# stm32f030f4p6_board.net
KiCad netlist of a schematic drawn in EasyEDA Pro
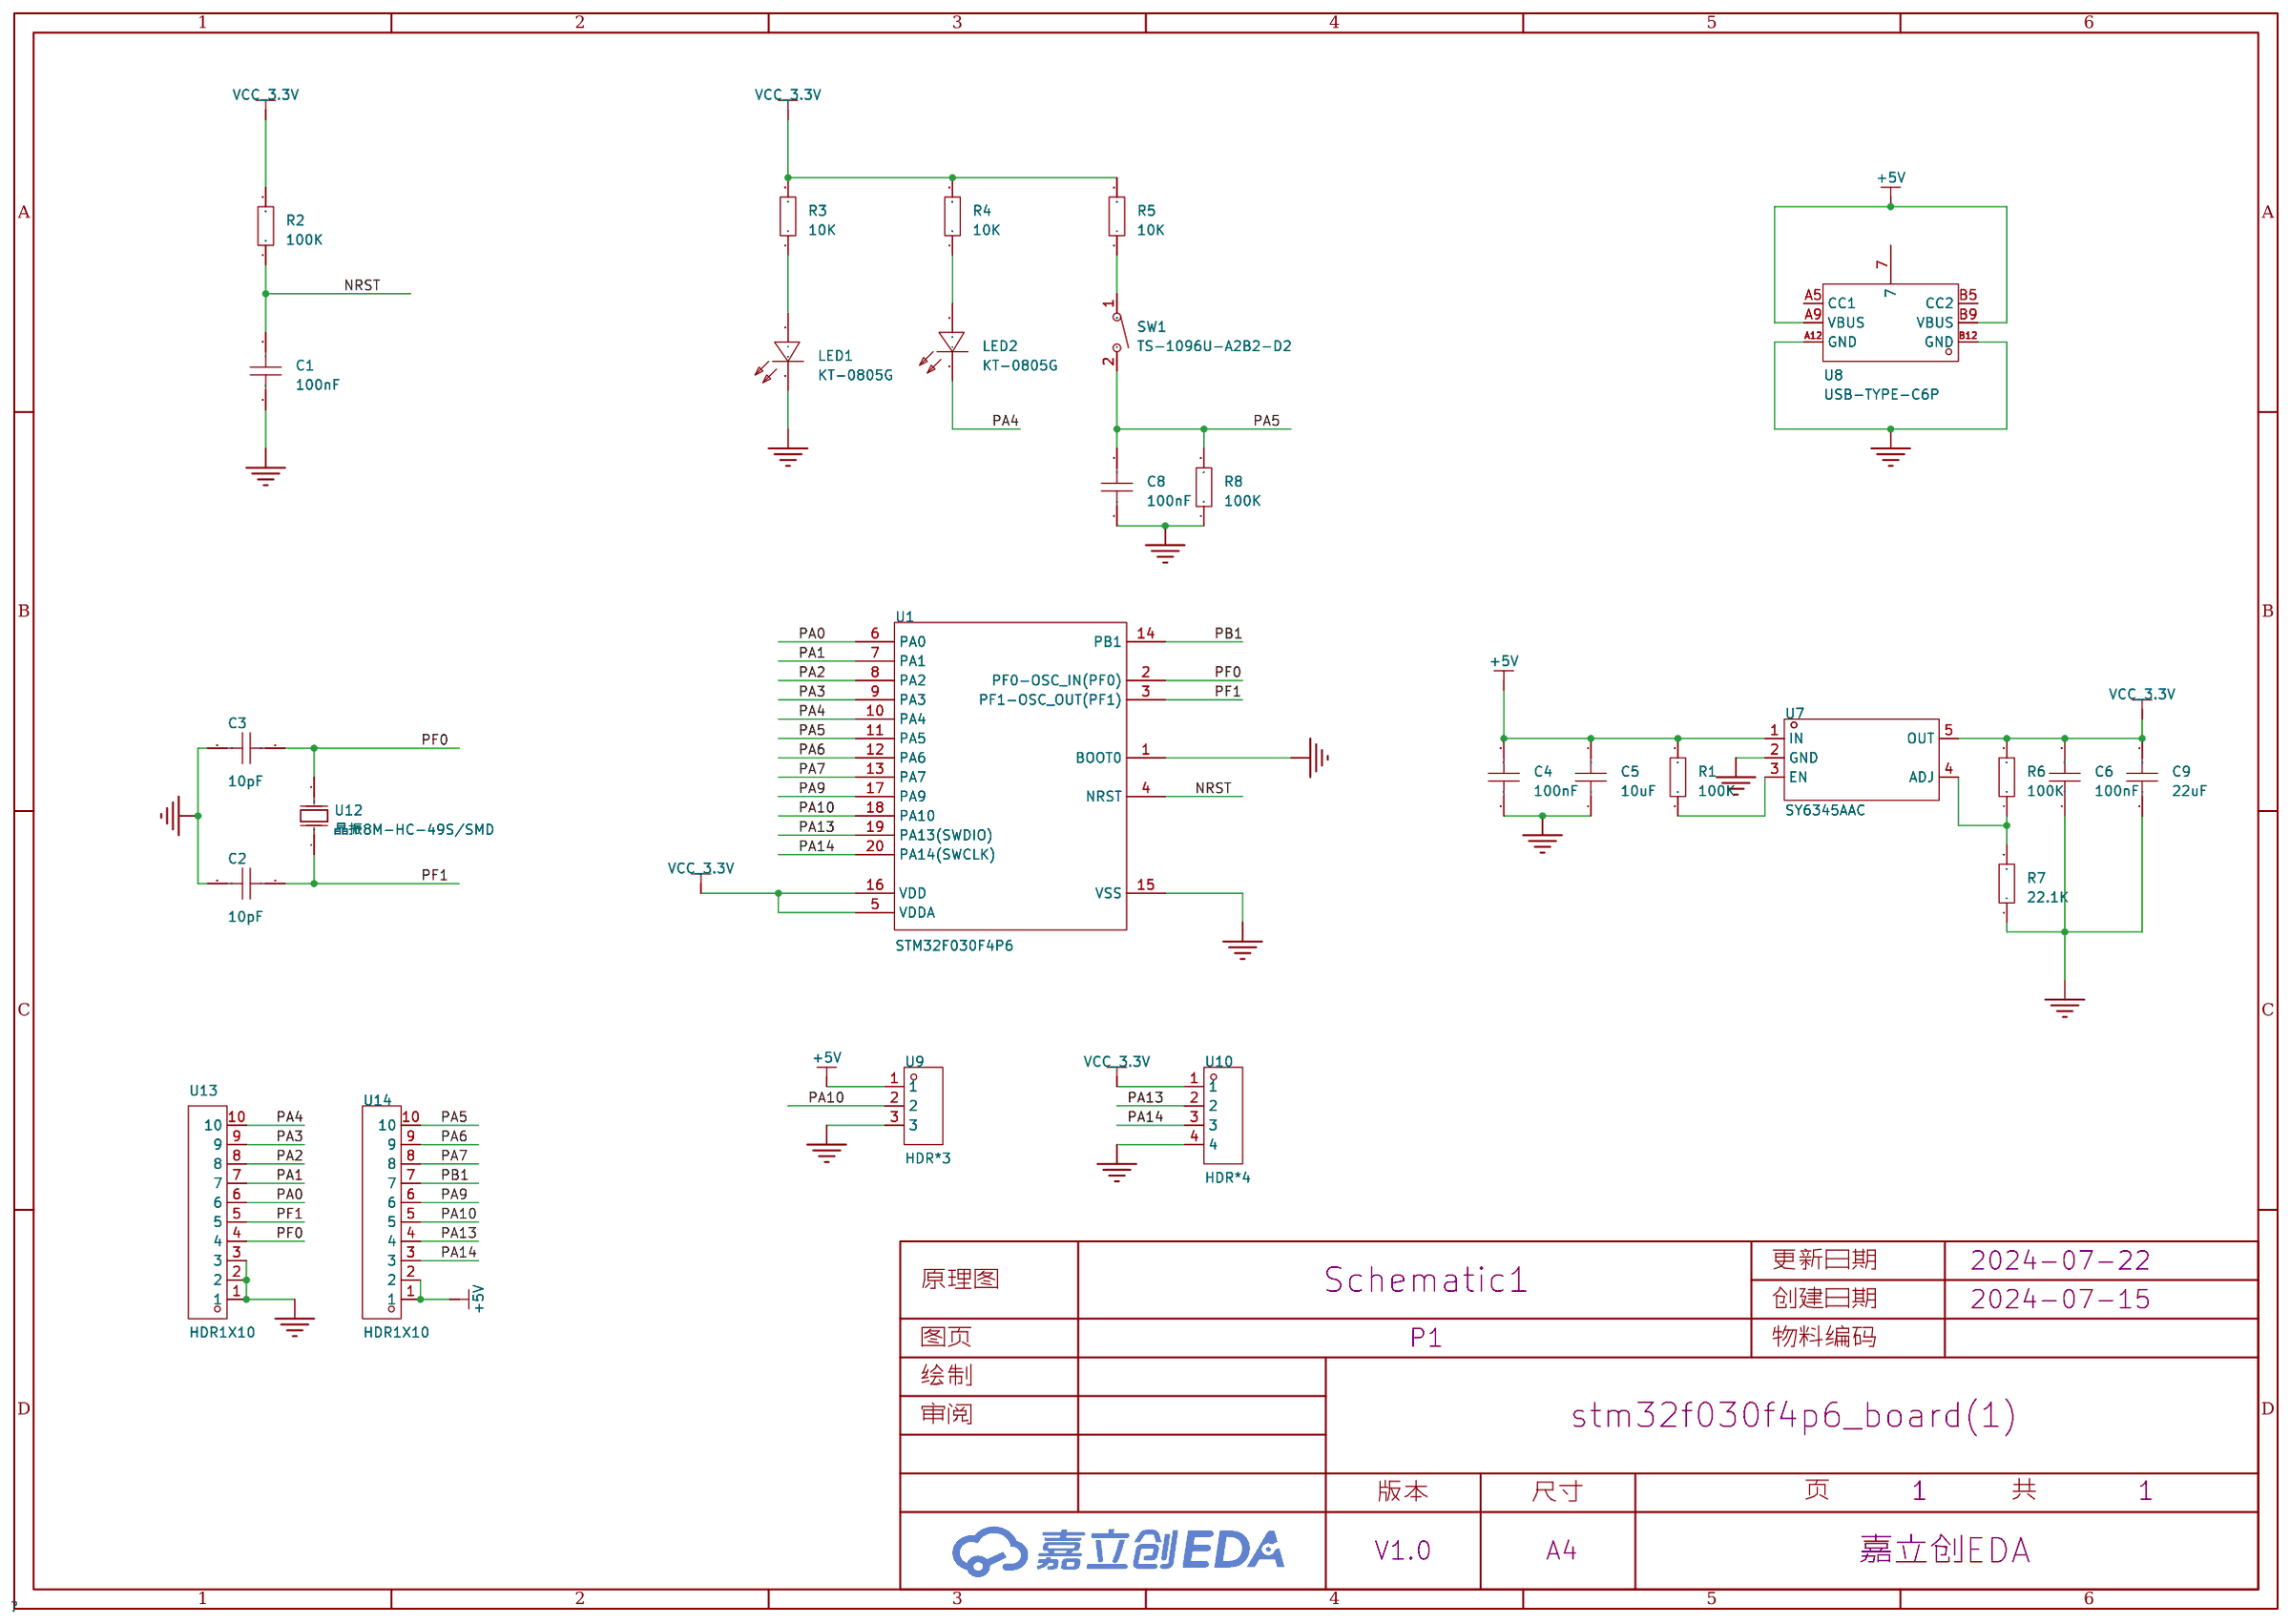
[diagram p0: schematic sheet]

(export (version "E")
  (design (tool "Eeschema 10.0.6"))
  (components
    (comp (ref "C1")
      (value "100nF")
      (footprint "easyedapro:C0805")
      (libsource (lib "easyedapro") (part "CapAcitance"))
    )
    (comp (ref "C2")
      (value "10pF")
      (footprint "easyedapro:C0805")
      (libsource (lib "easyedapro") (part "CapAcitance"))
    )
    (comp (ref "C3")
      (value "10pF")
      (footprint "easyedapro:C0805")
      (libsource (lib "easyedapro") (part "CapAcitance"))
    )
    (comp (ref "C4")
      (value "100nF")
      (footprint "easyedapro:C0805")
      (libsource (lib "easyedapro") (part "CapAcitance"))
    )
    (comp (ref "C5")
      (value "10uF")
      (footprint "easyedapro:C0805")
      (libsource (lib "easyedapro") (part "CapAcitance"))
    )
    (comp (ref "C6")
      (value "100nF")
      (footprint "easyedapro:C0805")
      (libsource (lib "easyedapro") (part "CapAcitance"))
    )
    (comp (ref "C8")
      (value "100nF")
      (footprint "easyedapro:C0805")
      (libsource (lib "easyedapro") (part "CapAcitance"))
    )
    (comp (ref "C9")
      (value "22uF")
      (footprint "easyedapro:C0805")
      (libsource (lib "easyedapro") (part "CapAcitance"))
    )
    (comp (ref "LED1")
      (value "KT-0805G")
      (footprint "easyedapro:LED0805-R-RD")
      (description "灯头类型:-;发光颜色:翠绿色;正向电压(VF):-;功率:-;正向电流:-;主波长:-;二极管配置:-;透镜颜色:-;色温:-;发光强度:-;发光角度:-;载带方式:-;工作温度:-;")
      (fields (field (name "Manufacturer") "KENTO"))
      (libsource (lib "easyedapro") (part "0805G (Green)"))
    )
    (comp (ref "LED2")
      (value "KT-0805G")
      (footprint "easyedapro:LED0805-R-RD")
      (description "灯头类型:-;发光颜色:翠绿色;正向电压(VF):-;功率:-;正向电流:-;主波长:-;二极管配置:-;透镜颜色:-;色温:-;发光强度:-;发光角度:-;载带方式:-;工作温度:-;")
      (fields (field (name "Manufacturer") "KENTO"))
      (libsource (lib "easyedapro") (part "0805G (Green)"))
    )
    (comp (ref "R1") (value "100K") (footprint "easyedapro:R0603") (libsource (lib "easyedapro") (part "电阻")))
    (comp (ref "R2") (value "100K") (footprint "easyedapro:R0603") (libsource (lib "easyedapro") (part "电阻")))
    (comp (ref "R3") (value "10K") (footprint "easyedapro:R0603") (libsource (lib "easyedapro") (part "电阻")))
    (comp (ref "R4") (value "10K") (footprint "easyedapro:R0603") (libsource (lib "easyedapro") (part "电阻")))
    (comp (ref "R5") (value "10K") (footprint "easyedapro:R0603") (libsource (lib "easyedapro") (part "电阻")))
    (comp (ref "R6") (value "100K") (footprint "easyedapro:R0603") (libsource (lib "easyedapro") (part "电阻")))
    (comp (ref "R7")
      (value "22.1K")
      (footprint "easyedapro:R0603")
      (libsource (lib "easyedapro") (part "电阻"))
    )
    (comp (ref "R8") (value "100K") (footprint "easyedapro:R0603") (libsource (lib "easyedapro") (part "电阻")))
    (comp (ref "SW1")
      (value "TS-1096U-A2B2-D2")
      (footprint "easyedapro:SW-SMD_L6.0-W3.3-LS6.7")
      (description "电路结构:单刀单掷;按钮形状:矩形按钮;作用力:180gf;安装方式:-;开关长度:6mm;开关宽度:3.3mm;开关高度:5mm;带灯:-;机械寿命:-;")
      (fields (field (name "Manufacturer") "Yuandi(元迪)"))
      (libsource (lib "easyedapro") (part "TS-1096U-A2B2-D2"))
    )
    (comp (ref "U1")
      (value "STM32F030F4P6")
      (footprint "easyedapro:TSSOP-20_L6.5-W4.4-P0.65-LS6.4-BL")
      (description "CPU内核:CM0;程序存储容量:16KB;RAM总容量:4KB;GPIO端口数量:15;工作电压范围:2.4V~3.6V;CPU最大主频:48MHz;程序存储器类型:FLASH;")
      (fields (field (name "Manufacturer") "ST(意法半导体)"))
      (libsource (lib "easyedapro") (part "STM32F030F4P6"))
    )
    (comp (ref "U7")
      (value "SY6345AAC")
      (footprint "easyedapro:SOT-23-5_L3.0-W1.7-P0.95-LS2.8-BR")
      (description "输出类型:-;")
      (fields (field (name "Manufacturer") "silergy(矽力杰)"))
      (libsource (lib "easyedapro") (part "SY6345AAC"))
    )
    (comp (ref "U8")
      (value "USB-TYPE-C6P")
      (footprint "easyedapro:TYPE-C-SMD_TYPE-C-6P-1")
      (libsource (lib "easyedapro") (part "USB-TYPE-C6P"))
    )
    (comp (ref "U9")
      (value "HDR*3")
      (footprint "easyedapro:HDR-TH_3P-P2.54-V-M-A")
      (fields (field (name "Manufacturer Part") "TXM_3"))
      (libsource (lib "easyedapro") (part "TXM_3"))
    )
    (comp (ref "U10")
      (value "HDR*4")
      (footprint "easyedapro:HDR-TH_4P-P2.54-V-F")
      (fields (field (name "Manufacturer Part") "HC-08蓝牙"))
      (libsource (lib "easyedapro") (part "HC-08蓝牙"))
    )
    (comp (ref "U12")
      (value "晶振8M-HC-49S/SMD")
      (footprint "easyedapro:HC-49S_L11.4-W4.8-LS12.7")
      (libsource (lib "easyedapro") (part "晶振8M-HC-49S/SMD"))
    )
    (comp (ref "U13")
      (value "HDR1X10")
      (footprint "easyedapro:HDR-TH_10P-P2.54-V-F_C9900008052")
      (libsource (lib "easyedapro") (part "HDR1X10"))
    )
    (comp (ref "U14")
      (value "HDR1X10")
      (footprint "easyedapro:HDR-TH_10P-P2.54-V-F_C9900008052")
      (libsource (lib "easyedapro") (part "HDR1X10"))
    )
  )
  (nets
    (net (code "1") (name "+5V") (class "Default")
      (node (ref "C4") (pin "2") (pinfunction "2_2") (pintype "input"))
      (node (ref "C5") (pin "2") (pinfunction "2_2") (pintype "input"))
      (node (ref "R1") (pin "1") (pinfunction "1_1") (pintype "input"))
      (node (ref "U14") (pin "1") (pinfunction "1_1") (pintype "unspecified"))
      (node (ref "U14") (pin "2") (pinfunction "2_2") (pintype "unspecified"))
      (node (ref "U7") (pin "1") (pinfunction "IN_1") (pintype "input"))
      (node (ref "U8") (pin "A9") (pinfunction "VBUS_A9") (pintype "input"))
      (node (ref "U8") (pin "B9") (pinfunction "VBUS_B9") (pintype "input"))
      (node (ref "U9") (pin "1") (pinfunction "1_1") (pintype "unspecified"))
    )
    (net (code "2") (name "/NRST") (class "Default")
      (node (ref "C1") (pin "2") (pinfunction "2_2") (pintype "input"))
      (node (ref "R2") (pin "1") (pinfunction "1_1") (pintype "input"))
      (node (ref "U1") (pin "4") (pinfunction "NRST_4") (pintype "bidirectional"))
    )
    (net (code "3") (name "/PA0") (class "Default")
      (node (ref "U1") (pin "6") (pinfunction "PA0_6") (pintype "bidirectional"))
      (node (ref "U13") (pin "6") (pinfunction "6_6") (pintype "unspecified"))
    )
    (net (code "4") (name "/PA1") (class "Default")
      (node (ref "U1") (pin "7") (pinfunction "PA1_7") (pintype "bidirectional"))
      (node (ref "U13") (pin "7") (pinfunction "7_7") (pintype "unspecified"))
    )
    (net (code "5") (name "/PA2") (class "Default")
      (node (ref "U1") (pin "8") (pinfunction "PA2_8") (pintype "bidirectional"))
      (node (ref "U13") (pin "8") (pinfunction "8_8") (pintype "unspecified"))
    )
    (net (code "6") (name "/PA3") (class "Default")
      (node (ref "U1") (pin "9") (pinfunction "PA3_9") (pintype "bidirectional"))
      (node (ref "U13") (pin "9") (pinfunction "9_9") (pintype "unspecified"))
    )
    (net (code "7") (name "/PA4") (class "Default")
      (node (ref "LED2") (pin "2") (pinfunction "K_2") (pintype "unspecified"))
      (node (ref "U1") (pin "10") (pinfunction "PA4_10") (pintype "bidirectional"))
      (node (ref "U13") (pin "10") (pinfunction "10_10") (pintype "unspecified"))
    )
    (net (code "8") (name "/PA5") (class "Default")
      (node (ref "C8") (pin "2") (pinfunction "2_2") (pintype "input"))
      (node (ref "R8") (pin "2") (pinfunction "2_2") (pintype "input"))
      (node (ref "SW1") (pin "2") (pinfunction "2_2") (pintype "unspecified"))
      (node (ref "U1") (pin "11") (pinfunction "PA5_11") (pintype "bidirectional"))
      (node (ref "U14") (pin "10") (pinfunction "10_10") (pintype "unspecified"))
    )
    (net (code "9") (name "/PA6") (class "Default")
      (node (ref "U1") (pin "12") (pinfunction "PA6_12") (pintype "bidirectional"))
      (node (ref "U14") (pin "9") (pinfunction "9_9") (pintype "unspecified"))
    )
    (net (code "10") (name "/PA7") (class "Default")
      (node (ref "U1") (pin "13") (pinfunction "PA7_13") (pintype "bidirectional"))
      (node (ref "U14") (pin "8") (pinfunction "8_8") (pintype "unspecified"))
    )
    (net (code "11") (name "/PA9") (class "Default")
      (node (ref "U1") (pin "17") (pinfunction "PA9_17") (pintype "bidirectional"))
      (node (ref "U14") (pin "6") (pinfunction "6_6") (pintype "unspecified"))
    )
    (net (code "12") (name "/PA10") (class "Default")
      (node (ref "U1") (pin "18") (pinfunction "PA10_18") (pintype "bidirectional"))
      (node (ref "U14") (pin "5") (pinfunction "5_5") (pintype "unspecified"))
      (node (ref "U9") (pin "2") (pinfunction "2_2") (pintype "unspecified"))
    )
    (net (code "13") (name "/PA13") (class "Default")
      (node (ref "U1") (pin "19") (pinfunction "PA13(SWDIO)_19") (pintype "bidirectional"))
      (node (ref "U10") (pin "2") (pinfunction "2_2") (pintype "unspecified"))
      (node (ref "U14") (pin "4") (pinfunction "4_4") (pintype "unspecified"))
    )
    (net (code "14") (name "/PA14") (class "Default")
      (node (ref "U1") (pin "20") (pinfunction "PA14(SWCLK)_20") (pintype "bidirectional"))
      (node (ref "U10") (pin "3") (pinfunction "3_3") (pintype "unspecified"))
      (node (ref "U14") (pin "3") (pinfunction "3_3") (pintype "unspecified"))
    )
    (net (code "15") (name "/PB1") (class "Default")
      (node (ref "U1") (pin "14") (pinfunction "PB1_14") (pintype "bidirectional"))
      (node (ref "U14") (pin "7") (pinfunction "7_7") (pintype "unspecified"))
    )
    (net (code "16") (name "/PF0") (class "Default")
      (node (ref "C3") (pin "1") (pinfunction "1_1") (pintype "input"))
      (node (ref "U1") (pin "2") (pinfunction "PF0-OSC_IN(PF0)_2") (pintype "bidirectional"))
      (node (ref "U12") (pin "2") (pinfunction "OSC2_2") (pintype "input"))
      (node (ref "U13") (pin "4") (pinfunction "4_4") (pintype "unspecified"))
    )
    (net (code "17") (name "/PF1") (class "Default")
      (node (ref "C2") (pin "1") (pinfunction "1_1") (pintype "input"))
      (node (ref "U1") (pin "3") (pinfunction "PF1-OSC_OUT(PF1)_3") (pintype "bidirectional"))
      (node (ref "U12") (pin "1") (pinfunction "OSC1_1") (pintype "input"))
      (node (ref "U13") (pin "5") (pinfunction "5_5") (pintype "unspecified"))
    )
    (net (code "18") (name "GND") (class "Default")
      (node (ref "C1") (pin "1") (pinfunction "1_1") (pintype "input"))
      (node (ref "C2") (pin "2") (pinfunction "2_2") (pintype "input"))
      (node (ref "C3") (pin "2") (pinfunction "2_2") (pintype "input"))
      (node (ref "C4") (pin "1") (pinfunction "1_1") (pintype "input"))
      (node (ref "C5") (pin "1") (pinfunction "1_1") (pintype "input"))
      (node (ref "C6") (pin "1") (pinfunction "1_1") (pintype "input"))
      (node (ref "C8") (pin "1") (pinfunction "1_1") (pintype "input"))
      (node (ref "C9") (pin "1") (pinfunction "1_1") (pintype "input"))
      (node (ref "LED1") (pin "2") (pinfunction "K_2") (pintype "unspecified"))
      (node (ref "R7") (pin "1") (pinfunction "1_1") (pintype "input"))
      (node (ref "R8") (pin "1") (pinfunction "1_1") (pintype "input"))
      (node (ref "U1") (pin "1") (pinfunction "BOOT0_1") (pintype "unspecified"))
      (node (ref "U1") (pin "15") (pinfunction "VSS_15") (pintype "unspecified"))
      (node (ref "U10") (pin "4") (pinfunction "4_4") (pintype "unspecified"))
      (node (ref "U13") (pin "1") (pinfunction "1_1") (pintype "unspecified"))
      (node (ref "U13") (pin "2") (pinfunction "2_2") (pintype "unspecified"))
      (node (ref "U13") (pin "3") (pinfunction "3_3") (pintype "unspecified"))
      (node (ref "U7") (pin "2") (pinfunction "GND_2") (pintype "input"))
      (node (ref "U8") (pin "A12") (pinfunction "GND_A12") (pintype "input"))
      (node (ref "U8") (pin "B12") (pinfunction "GND_B12") (pintype "input"))
      (node (ref "U9") (pin "3") (pinfunction "3_3") (pintype "unspecified"))
    )
    (net (code "19") (name "Net-(LED1-A)") (class "Default")
      (node (ref "LED1") (pin "1") (pinfunction "A_1") (pintype "unspecified"))
      (node (ref "R3") (pin "1") (pinfunction "1_1") (pintype "input"))
    )
    (net (code "20") (name "Net-(LED2-A)") (class "Default")
      (node (ref "LED2") (pin "1") (pinfunction "A_1") (pintype "unspecified"))
      (node (ref "R4") (pin "1") (pinfunction "1_1") (pintype "input"))
    )
    (net (code "21") (name "Net-(R5-Pad1)") (class "Default")
      (node (ref "R5") (pin "1") (pinfunction "1_1") (pintype "input"))
      (node (ref "SW1") (pin "1") (pinfunction "1_1") (pintype "unspecified"))
    )
    (net (code "22") (name "Net-(U7-ADJ)") (class "Default")
      (node (ref "R6") (pin "1") (pinfunction "1_1") (pintype "input"))
      (node (ref "R7") (pin "2") (pinfunction "2_2") (pintype "input"))
      (node (ref "U7") (pin "4") (pinfunction "ADJ_4") (pintype "input"))
    )
    (net (code "23") (name "Net-(U7-EN)") (class "Default")
      (node (ref "R1") (pin "2") (pinfunction "2_2") (pintype "input"))
      (node (ref "U7") (pin "3") (pinfunction "EN_3") (pintype "input"))
    )
    (net (code "24") (name "VCC_3.3V") (class "Default")
      (node (ref "C6") (pin "2") (pinfunction "2_2") (pintype "input"))
      (node (ref "C9") (pin "2") (pinfunction "2_2") (pintype "input"))
      (node (ref "R2") (pin "2") (pinfunction "2_2") (pintype "input"))
      (node (ref "R3") (pin "2") (pinfunction "2_2") (pintype "input"))
      (node (ref "R4") (pin "2") (pinfunction "2_2") (pintype "input"))
      (node (ref "R5") (pin "2") (pinfunction "2_2") (pintype "input"))
      (node (ref "R6") (pin "2") (pinfunction "2_2") (pintype "input"))
      (node (ref "U1") (pin "16") (pinfunction "VDD_16") (pintype "unspecified"))
      (node (ref "U1") (pin "5") (pinfunction "VDDA_5") (pintype "unspecified"))
      (node (ref "U10") (pin "1") (pinfunction "1_1") (pintype "unspecified"))
      (node (ref "U7") (pin "5") (pinfunction "OUT_5") (pintype "input"))
    )
    (net (code "25") (name "unconnected-(U8-CC1-PadA5)") (class "Default")
      (node (ref "U8") (pin "A5") (pinfunction "CC1_A5") (pintype "input"))
    )
    (net (code "26") (name "unconnected-(U8-CC2-PadB5)") (class "Default")
      (node (ref "U8") (pin "B5") (pinfunction "CC2_B5") (pintype "input"))
    )
    (net (code "27") (name "unconnected-(U8-Pad7)") (class "Default")
      (node (ref "U8") (pin "7") (pinfunction "7_7") (pintype "input"))
    )
  )
)
